# PROC099B_QSPI_Flash_Reference.net
KiCad netlist of a schematic drawn in Altium Designer
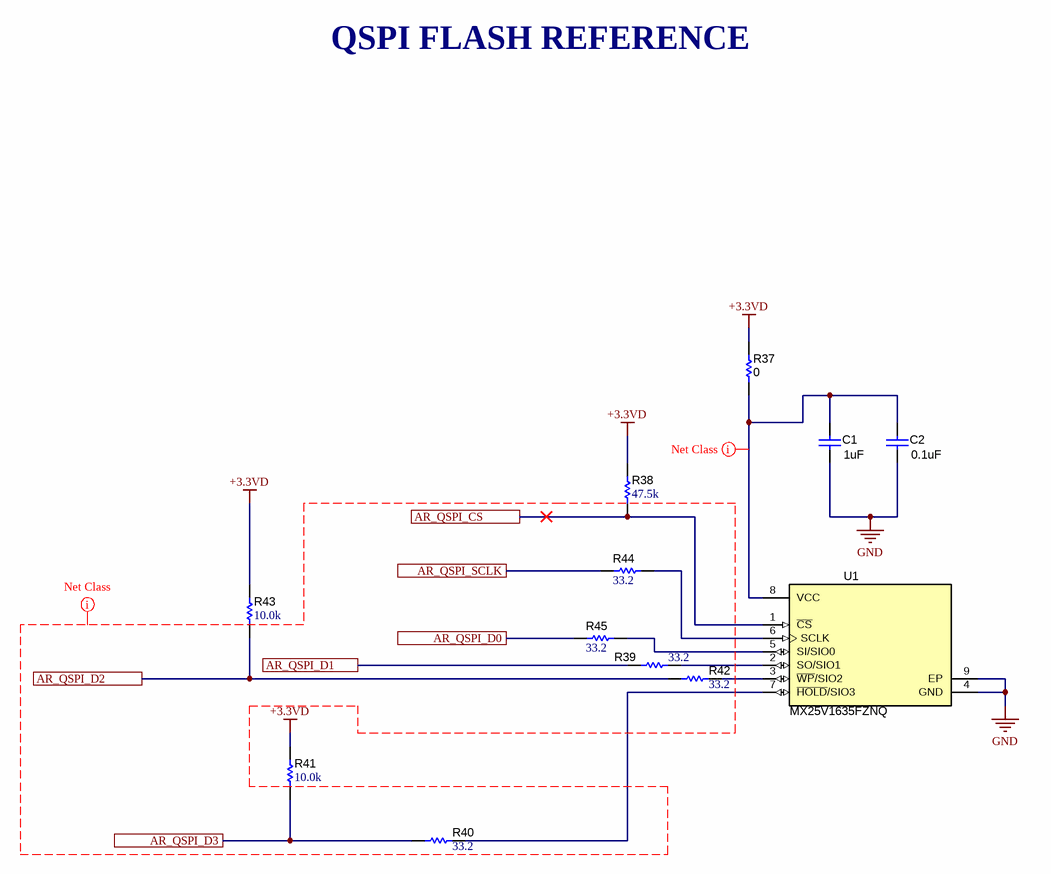
[diagram p0: PROC099B_QSPI_Flash_Reference.SchDoc]

(export (version "E")
  (design (tool "Eeschema 10.0.6"))
  (components
    (comp (ref "C1")
      (value "GCM188R71C105KA64D")
      (footprint "0603")
      (description "CAP, CERM, 1 uF, 16 V, +/- 10%, X7R, AEC-Q200 Grade 1, 0603")
      (fields
        (field (name "MANUFACTURER") "MuRata")
        (field (name "VALUEDISPLAYED") "1uF")
        (field (name "PUBLISHER") "Texas Instruments")
      )
      (libsource (lib "Altium Vault - TI") (part "Capacitor"))
    )
    (comp (ref "C2")
      (value "CGA2B3X7R1H104K050BB")
      (footprint "0402L")
      (description "CAP, CERM, 0.1 uF, 50 V, +/- 10%, X7R, AEC-Q200 Grade 1, 0402")
      (fields
        (field (name "MANUFACTURER") "TDK")
        (field (name "VALUEDISPLAYED") "0.1uF")
        (field (name "PUBLISHER") "Texas Instruments")
      )
      (libsource (lib "Altium Vault - TI") (part "Capacitor"))
    )
    (comp (ref "R37")
      (value "ERJ-2GE0R00X")
      (footprint "0402L")
      (description "RES, 0, 5%, 0.063 W, 0402")
      (fields
        (field (name "MANUFACTURER") "Panasonic")
        (field (name "VALUEDISPLAYED") "0")
        (field (name "PUBLISHER") "Texas Instruments")
      )
      (libsource (lib "Altium Vault - TI") (part "Resistor"))
    )
    (comp (ref "R38")
      (value "CRCW040247K5FKED")
      (footprint "0402L")
      (description "RES, 47.5 k, 1%, 0.063 W, AEC-Q200 Grade 0, 0402")
      (fields (field (name "MANUFACTURER") "Vishay-Dale") (field (name "VALUEDISPLAYED") "47.5k"))
      (libsource (lib "Altium Vault - TI") (part "Resistor"))
    )
    (comp (ref "R39")
      (value "CRCW020133R2FNED")
      (footprint "0201_Silk")
      (description "RES, 33.2, 1%, 0.05 W, 0201")
      (fields (field (name "MANUFACTURER") "Vishay-Dale") (field (name "VALUEDISPLAYED") "33.2"))
      (libsource (lib "Altium Vault - TI") (part "Resistor"))
    )
    (comp (ref "R40")
      (value "CRCW020133R2FNED")
      (footprint "0201_Silk")
      (description "RES, 33.2, 1%, 0.05 W, 0201")
      (fields (field (name "MANUFACTURER") "Vishay-Dale") (field (name "VALUEDISPLAYED") "33.2"))
      (libsource (lib "Altium Vault - TI") (part "Resistor"))
    )
    (comp (ref "R41")
      (value "CRCW040210K0FKED")
      (footprint "0402L")
      (description "RES, 10.0 k, 1%, 0.063 W, AEC-Q200 Grade 0, 0402")
      (fields (field (name "MANUFACTURER") "Vishay-Dale") (field (name "VALUEDISPLAYED") "10.0k"))
      (libsource (lib "Altium Vault - TI") (part "Resistor"))
    )
    (comp (ref "R42")
      (value "CRCW020133R2FNED")
      (footprint "0201_Silk")
      (description "RES, 33.2, 1%, 0.05 W, 0201")
      (fields (field (name "MANUFACTURER") "Vishay-Dale") (field (name "VALUEDISPLAYED") "33.2"))
      (libsource (lib "Altium Vault - TI") (part "Resistor"))
    )
    (comp (ref "R43")
      (value "CRCW040210K0FKED")
      (footprint "0402L")
      (description "RES, 10.0 k, 1%, 0.063 W, AEC-Q200 Grade 0, 0402")
      (fields (field (name "MANUFACTURER") "Vishay-Dale") (field (name "VALUEDISPLAYED") "10.0k"))
      (libsource (lib "Altium Vault - TI") (part "Resistor"))
    )
    (comp (ref "R44")
      (value "CRCW020133R2FNED")
      (footprint "0201_Silk")
      (description "RES, 33.2, 1%, 0.05 W, 0201")
      (fields (field (name "MANUFACTURER") "Vishay-Dale") (field (name "VALUEDISPLAYED") "33.2"))
      (libsource (lib "Altium Vault - TI") (part "Resistor"))
    )
    (comp (ref "R45")
      (value "CRCW020133R2FNED")
      (footprint "0201_Silk")
      (description "RES, 33.2, 1%, 0.05 W, 0201")
      (fields (field (name "MANUFACTURER") "Vishay-Dale") (field (name "VALUEDISPLAYED") "33.2"))
      (libsource (lib "Altium Vault - TI") (part "Resistor"))
    )
    (comp (ref "U1")
      (value "MX25V1635FZNQ")
      (footprint "WSON-8L_6x5MM_EP")
      (description "2.3V-3.6V, 16M-BIT [x 1/x 2/x 4] CMOS FLASH Memory, WSON-8")
      (fields (field (name "MANUFACTURER") "Macronix International Co., LTD"))
      (libsource (lib "Altium Vault - TI") (part "MX25V1635FZ"))
    )
  )
  (nets
    (net (code "1") (name "+3.3VD") (class "Default")
      (node (ref "R37") (pin "1") (pinfunction "1_1") (pintype "passive"))
      (node (ref "R38") (pin "2") (pinfunction "2_2") (pintype "passive"))
      (node (ref "R41") (pin "2") (pinfunction "2_2") (pintype "passive"))
      (node (ref "R43") (pin "2") (pinfunction "2_2") (pintype "passive"))
    )
    (net (code "2") (name "/AR_QSPI_CS") (class "Default")
      (node (ref "R38") (pin "1") (pinfunction "1_1") (pintype "passive"))
      (node (ref "U1") (pin "1") (pinfunction "CS_1") (pintype "input"))
    )
    (net (code "3") (name "/AR_QSPI_D0") (class "Default")
      (node (ref "R45") (pin "2") (pinfunction "2_2") (pintype "passive"))
    )
    (net (code "4") (name "/AR_QSPI_D1") (class "Default")
      (node (ref "R39") (pin "1") (pinfunction "1_1") (pintype "passive"))
    )
    (net (code "5") (name "/AR_QSPI_D2") (class "Default")
      (node (ref "R42") (pin "1") (pinfunction "1_1") (pintype "passive"))
      (node (ref "R43") (pin "1") (pinfunction "1_1") (pintype "passive"))
    )
    (net (code "6") (name "/AR_QSPI_D3") (class "Default")
      (node (ref "R40") (pin "2") (pinfunction "2_2") (pintype "passive"))
      (node (ref "R41") (pin "1") (pinfunction "1_1") (pintype "passive"))
    )
    (net (code "7") (name "/AR_QSPI_SCLK") (class "Default")
      (node (ref "R44") (pin "2") (pinfunction "2_2") (pintype "passive"))
    )
    (net (code "8") (name "GND") (class "Default")
      (node (ref "C1") (pin "1") (pinfunction "1_1") (pintype "passive"))
      (node (ref "C2") (pin "1") (pinfunction "1_1") (pintype "passive"))
      (node (ref "U1") (pin "4") (pinfunction "GND_4") (pintype "power_in"))
      (node (ref "U1") (pin "9") (pinfunction "EP_9") (pintype "passive"))
    )
    (net (code "9") (name "Net-(U1-SCLK)") (class "Default")
      (node (ref "R44") (pin "1") (pinfunction "1_1") (pintype "passive"))
      (node (ref "U1") (pin "6") (pinfunction "SCLK_6") (pintype "input"))
    )
    (net (code "10") (name "Net-(U1-SI{slash}SIO0)") (class "Default")
      (node (ref "R45") (pin "1") (pinfunction "1_1") (pintype "passive"))
      (node (ref "U1") (pin "5") (pinfunction "SI/SIO0_5") (pintype "bidirectional"))
    )
    (net (code "11") (name "Net-(U1-SO{slash}SIO1)") (class "Default")
      (node (ref "R39") (pin "2") (pinfunction "2_2") (pintype "passive"))
      (node (ref "U1") (pin "2") (pinfunction "SO/SIO1_2") (pintype "bidirectional"))
    )
    (net (code "12") (name "Net-(U1-VCC)") (class "Default")
      (node (ref "C1") (pin "2") (pinfunction "2_2") (pintype "passive"))
      (node (ref "C2") (pin "2") (pinfunction "2_2") (pintype "passive"))
      (node (ref "R37") (pin "2") (pinfunction "2_2") (pintype "passive"))
      (node (ref "U1") (pin "8") (pinfunction "VCC_8") (pintype "power_in"))
    )
    (net (code "13") (name "Net-(U1-~{HOLD}{slash}SIO3)") (class "Default")
      (node (ref "R40") (pin "1") (pinfunction "1_1") (pintype "passive"))
      (node (ref "U1") (pin "7") (pinfunction "~{HOLD}/SIO3_7") (pintype "bidirectional"))
    )
    (net (code "14") (name "Net-(U1-~{WP}{slash}SIO2)") (class "Default")
      (node (ref "R42") (pin "2") (pinfunction "2_2") (pintype "passive"))
      (node (ref "U1") (pin "3") (pinfunction "~{WP}/SIO2_3") (pintype "bidirectional"))
    )
  )
)
